# Sheet2.net
KiCad netlist of a schematic drawn in Altium Designer
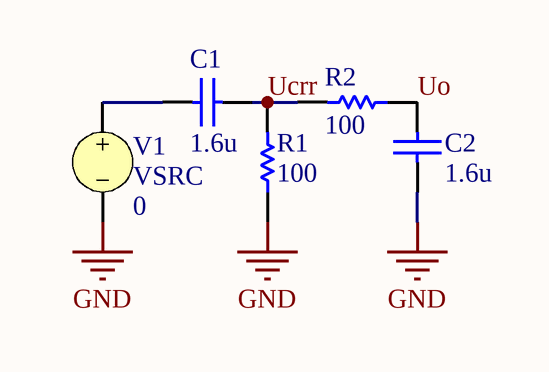
[diagram p0: Sheet2.SchDoc]

(export (version "E")
  (design (tool "Eeschema 10.0.6"))
  (components
    (comp (ref "C1")
      (value "1.6u")
      (description "Capacitor")
      (libsource (lib "Simulation Generic Components") (part "Capacitor"))
    )
    (comp (ref "C2")
      (value "1.6u")
      (description "Capacitor")
      (libsource (lib "Simulation Generic Components") (part "Capacitor"))
    )
    (comp (ref "R1")
      (value "100")
      (description "Resistor")
      (libsource (lib "Simulation Generic Components") (part "Resistor"))
    )
    (comp (ref "R2")
      (value "100")
      (description "Resistor")
      (libsource (lib "Simulation Generic Components") (part "Resistor"))
    )
    (comp (ref "V1")
      (value "VSRC")
      (description "Voltage Source")
      (fields (field (name "DC MAGNITUDE") "0") (field (name "PUBLISHER") "Altium Limited"))
      (libsource (lib "Simulation Generic Components") (part "VSRC"))
    )
  )
  (nets
    (net (code "1") (name "/Ucrr") (class "Default")
      (node (ref "C1") (pin "2") (pinfunction "2_2") (pintype "passive"))
      (node (ref "R1") (pin "2") (pinfunction "2_2") (pintype "passive"))
      (node (ref "R2") (pin "2") (pinfunction "2_2") (pintype "passive"))
    )
    (net (code "2") (name "/Uo") (class "Default")
      (node (ref "C2") (pin "2") (pinfunction "2_2") (pintype "passive"))
      (node (ref "R2") (pin "1") (pinfunction "1_1") (pintype "passive"))
    )
    (net (code "3") (name "GND") (class "Default")
      (node (ref "C2") (pin "1") (pinfunction "1_1") (pintype "passive"))
      (node (ref "R1") (pin "1") (pinfunction "1_1") (pintype "passive"))
      (node (ref "V1") (pin "2") (pinfunction "2_2") (pintype "passive"))
    )
    (net (code "4") (name "Net-(C1-Pad1)") (class "Default")
      (node (ref "C1") (pin "1") (pinfunction "1_1") (pintype "passive"))
      (node (ref "V1") (pin "1") (pinfunction "1_1") (pintype "passive"))
    )
  )
)
